# DPPXHK_SERVO.net
KiCad netlist of a schematic drawn in Altium Designer
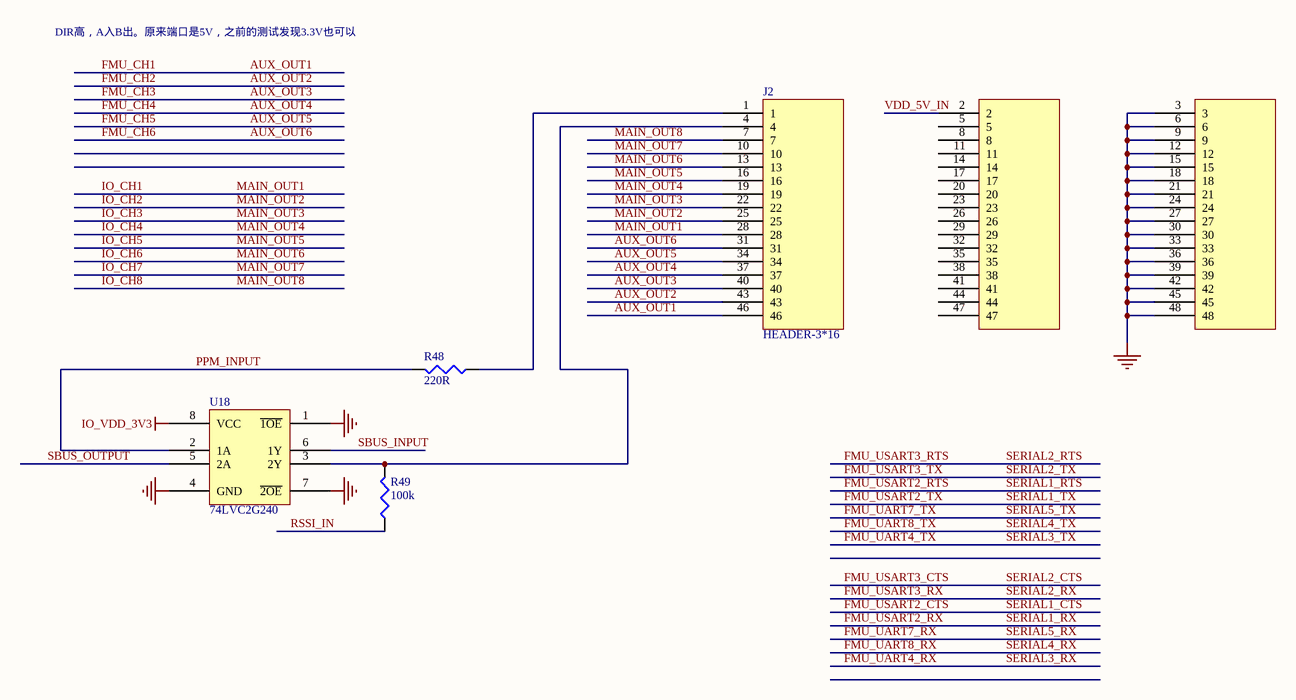
[diagram p0: DPPXHK_SERVO.SCHDOC]

(export (version "E")
  (design (tool "Eeschema 10.0.6"))
  (components
    (comp (ref "J2")
      (value "HEADER-3*16")
      (footprint "3X16RA")
      (libsource (lib "PX4FMUv2.4.6") (part "HEADER-3*16"))
    )
    (comp (ref "R48")
      (value "220R")
      (footprint "0402R")
      (description "Resistor")
      (fields (field (name "PUBLISHER") "Altium Limited"))
      (libsource (lib "Miscellaneous Devices") (part "Res3"))
    )
    (comp (ref "R49")
      (value "100k")
      (footprint "0402R")
      (description "Resistor")
      (fields (field (name "PUBLISHER") "Altium Limited"))
      (libsource (lib "Miscellaneous Devices") (part "Res3"))
    )
    (comp (ref "U18") (value "74LVC2G240") (footprint "TSSOP_8") (libsource (lib "PXHK") (part "74LVC2G240")))
  )
  (nets
    (net (code "1") (name "/AUX_OUT1") (class "Default")
      (node (ref "J2") (pin "46") (pinfunction "46_46") (pintype "passive"))
    )
    (net (code "2") (name "/AUX_OUT2") (class "Default")
      (node (ref "J2") (pin "43") (pinfunction "43_43") (pintype "passive"))
    )
    (net (code "3") (name "/AUX_OUT3") (class "Default")
      (node (ref "J2") (pin "40") (pinfunction "40_40") (pintype "passive"))
    )
    (net (code "4") (name "/AUX_OUT4") (class "Default")
      (node (ref "J2") (pin "37") (pinfunction "37_37") (pintype "passive"))
    )
    (net (code "5") (name "/AUX_OUT5") (class "Default")
      (node (ref "J2") (pin "34") (pinfunction "34_34") (pintype "passive"))
    )
    (net (code "6") (name "/AUX_OUT6") (class "Default")
      (node (ref "J2") (pin "31") (pinfunction "31_31") (pintype "passive"))
    )
    (net (code "21") (name "/IO_CH1") (class "Default")
      (node (ref "J2") (pin "28") (pinfunction "28_28") (pintype "passive"))
    )
    (net (code "22") (name "/IO_CH2") (class "Default")
      (node (ref "J2") (pin "25") (pinfunction "25_25") (pintype "passive"))
    )
    (net (code "23") (name "/IO_CH3") (class "Default")
      (node (ref "J2") (pin "22") (pinfunction "22_22") (pintype "passive"))
    )
    (net (code "24") (name "/IO_CH4") (class "Default")
      (node (ref "J2") (pin "19") (pinfunction "19_19") (pintype "passive"))
    )
    (net (code "25") (name "/IO_CH5") (class "Default")
      (node (ref "J2") (pin "16") (pinfunction "16_16") (pintype "passive"))
    )
    (net (code "26") (name "/IO_CH6") (class "Default")
      (node (ref "J2") (pin "13") (pinfunction "13_13") (pintype "passive"))
    )
    (net (code "27") (name "/IO_CH7") (class "Default")
      (node (ref "J2") (pin "10") (pinfunction "10_10") (pintype "passive"))
    )
    (net (code "28") (name "/IO_CH8") (class "Default")
      (node (ref "J2") (pin "7") (pinfunction "7_7") (pintype "passive"))
    )
    (net (code "29") (name "/PPM_INPUT") (class "Default")
      (node (ref "R48") (pin "2") (pinfunction "2_2") (pintype "passive"))
      (node (ref "U18") (pin "2") (pinfunction "1A_2") (pintype "passive"))
    )
    (net (code "30") (name "/RSSI_IN") (class "Default")
      (node (ref "R49") (pin "1") (pinfunction "1_1") (pintype "passive"))
    )
    (net (code "31") (name "/SBUS_INPUT") (class "Default")
      (node (ref "U18") (pin "6") (pinfunction "1Y_6") (pintype "passive"))
    )
    (net (code "32") (name "/SBUS_OUTPUT") (class "Default")
      (node (ref "U18") (pin "5") (pinfunction "2A_5") (pintype "passive"))
    )
    (net (code "33") (name "/VDD_5V_IN") (class "Default")
      (node (ref "J2") (pin "2") (pinfunction "2_2") (pintype "passive"))
    )
    (net (code "34") (name "GND") (class "Default")
      (node (ref "J2") (pin "12") (pinfunction "12_12") (pintype "passive"))
      (node (ref "J2") (pin "15") (pinfunction "15_15") (pintype "passive"))
      (node (ref "J2") (pin "18") (pinfunction "18_18") (pintype "passive"))
      (node (ref "J2") (pin "21") (pinfunction "21_21") (pintype "passive"))
      (node (ref "J2") (pin "24") (pinfunction "24_24") (pintype "passive"))
      (node (ref "J2") (pin "27") (pinfunction "27_27") (pintype "passive"))
      (node (ref "J2") (pin "3") (pinfunction "3_3") (pintype "passive"))
      (node (ref "J2") (pin "30") (pinfunction "30_30") (pintype "passive"))
      (node (ref "J2") (pin "33") (pinfunction "33_33") (pintype "passive"))
      (node (ref "J2") (pin "36") (pinfunction "36_36") (pintype "passive"))
      (node (ref "J2") (pin "39") (pinfunction "39_39") (pintype "passive"))
      (node (ref "J2") (pin "42") (pinfunction "42_42") (pintype "passive"))
      (node (ref "J2") (pin "45") (pinfunction "45_45") (pintype "passive"))
      (node (ref "J2") (pin "48") (pinfunction "48_48") (pintype "passive"))
      (node (ref "J2") (pin "6") (pinfunction "6_6") (pintype "passive"))
      (node (ref "J2") (pin "9") (pinfunction "9_9") (pintype "passive"))
      (node (ref "U18") (pin "1") (pinfunction "~{1OE}_1") (pintype "passive"))
      (node (ref "U18") (pin "4") (pinfunction "GND_4") (pintype "passive"))
      (node (ref "U18") (pin "7") (pinfunction "~{2OE}_7") (pintype "passive"))
    )
    (net (code "35") (name "IO_VDD_3V3") (class "Default")
      (node (ref "U18") (pin "8") (pinfunction "VCC_8") (pintype "passive"))
    )
    (net (code "36") (name "Net-(J2-Pad1)") (class "Default")
      (node (ref "J2") (pin "1") (pinfunction "1_1") (pintype "passive"))
      (node (ref "R48") (pin "1") (pinfunction "1_1") (pintype "passive"))
    )
    (net (code "37") (name "Net-(U18-2Y)") (class "Default")
      (node (ref "J2") (pin "4") (pinfunction "4_4") (pintype "passive"))
      (node (ref "R49") (pin "2") (pinfunction "2_2") (pintype "passive"))
      (node (ref "U18") (pin "3") (pinfunction "2Y_3") (pintype "passive"))
    )
    (net (code "38") (name "unconnected-(J2-Pad5)") (class "Default")
      (node (ref "J2") (pin "5") (pinfunction "5_5") (pintype "passive"))
    )
    (net (code "39") (name "unconnected-(J2-Pad8)") (class "Default")
      (node (ref "J2") (pin "8") (pinfunction "8_8") (pintype "passive"))
    )
    (net (code "40") (name "unconnected-(J2-Pad11)") (class "Default")
      (node (ref "J2") (pin "11") (pinfunction "11_11") (pintype "passive"))
    )
    (net (code "41") (name "unconnected-(J2-Pad14)") (class "Default")
      (node (ref "J2") (pin "14") (pinfunction "14_14") (pintype "passive"))
    )
    (net (code "42") (name "unconnected-(J2-Pad17)") (class "Default")
      (node (ref "J2") (pin "17") (pinfunction "17_17") (pintype "passive"))
    )
    (net (code "43") (name "unconnected-(J2-Pad20)") (class "Default")
      (node (ref "J2") (pin "20") (pinfunction "20_20") (pintype "passive"))
    )
    (net (code "44") (name "unconnected-(J2-Pad23)") (class "Default")
      (node (ref "J2") (pin "23") (pinfunction "23_23") (pintype "passive"))
    )
    (net (code "45") (name "unconnected-(J2-Pad26)") (class "Default")
      (node (ref "J2") (pin "26") (pinfunction "26_26") (pintype "passive"))
    )
    (net (code "46") (name "unconnected-(J2-Pad29)") (class "Default")
      (node (ref "J2") (pin "29") (pinfunction "29_29") (pintype "passive"))
    )
    (net (code "47") (name "unconnected-(J2-Pad32)") (class "Default")
      (node (ref "J2") (pin "32") (pinfunction "32_32") (pintype "passive"))
    )
    (net (code "48") (name "unconnected-(J2-Pad35)") (class "Default")
      (node (ref "J2") (pin "35") (pinfunction "35_35") (pintype "passive"))
    )
    (net (code "49") (name "unconnected-(J2-Pad38)") (class "Default")
      (node (ref "J2") (pin "38") (pinfunction "38_38") (pintype "passive"))
    )
    (net (code "50") (name "unconnected-(J2-Pad41)") (class "Default")
      (node (ref "J2") (pin "41") (pinfunction "41_41") (pintype "passive"))
    )
    (net (code "51") (name "unconnected-(J2-Pad44)") (class "Default")
      (node (ref "J2") (pin "44") (pinfunction "44_44") (pintype "passive"))
    )
    (net (code "52") (name "unconnected-(J2-Pad47)") (class "Default")
      (node (ref "J2") (pin "47") (pinfunction "47_47") (pintype "passive"))
    )
  )
)
